# Schematic.net
KiCad netlist of a schematic drawn in Altium Designer
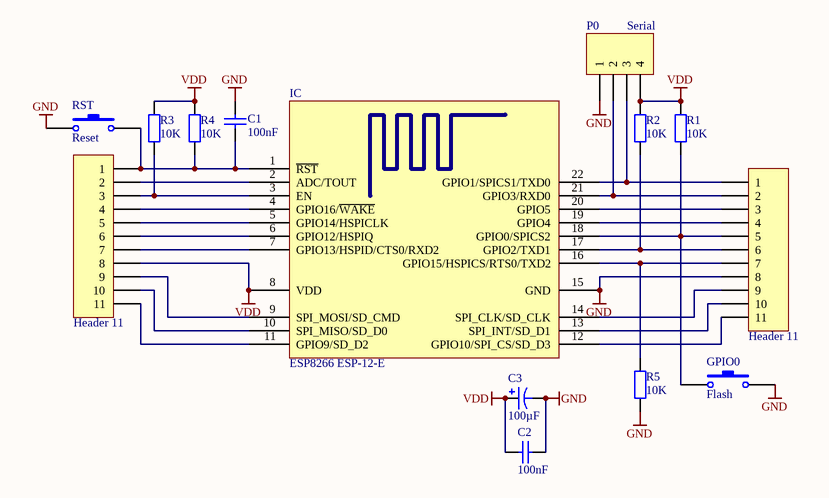
[diagram p0: Schematic.SchDoc]

(export (version "E")
  (design (tool "Eeschema 10.0.6"))
  (components
    (comp (ref "C1")
      (value "100nF")
      (footprint "C1206")
      (description "Capacitor (Semiconductor SIM Model)")
      (fields (field (name "Comment") "Cap Semi") (field (name "PUBLISHER") "Altium Limited"))
      (libsource (lib "Miscellaneous Devices") (part "Cap Semi"))
    )
    (comp (ref "C2")
      (value "100nF")
      (footprint "C1206")
      (description "Capacitor (Semiconductor SIM Model)")
      (fields (field (name "Comment") "Cap Semi") (field (name "PUBLISHER") "Altium Limited"))
      (libsource (lib "Miscellaneous Devices") (part "Cap Semi"))
    )
    (comp (ref "C3")
      (value "100µF")
      (footprint "SMD cap 6x5")
      (description "Polarized Capacitor (Radial)")
      (fields (field (name "PUBLISHER") "Altium Limited"))
      (libsource (lib "Miscellaneous Devices") (part "Cap Pol1"))
    )
    (comp (ref "GPIO0")
      (value "Flash")
      (footprint "SMDswitch")
      (description "Switch")
      (fields (field (name "PUBLISHER") "Altium Limited"))
      (libsource (lib "Miscellaneous Devices") (part "SW-PB"))
    )
    (comp (ref "IC")
      (value "ESP8266 ESP-12-E")
      (footprint "ESP8266 ESP-12-E")
      (libsource (lib "ESP8266") (part "ESP8266 ESP-12-E"))
    )
    (comp (ref "P0")
      (value "Serial")
      (footprint "HDR1X4")
      (description "Header, 4-Pin")
      (fields (field (name "PUBLISHER") "Altium Limited"))
      (libsource (lib "Miscellaneous Connectors") (part "Header 4"))
    )
    (comp (ref "P1")
      (value "Header 11")
      (footprint "HDR1X11")
      (description "Header, 11-Pin")
      (fields (field (name "PUBLISHER") "Altium Limited"))
      (libsource (lib "Miscellaneous Connectors") (part "Header 11"))
    )
    (comp (ref "P2")
      (value "Header 11")
      (footprint "HDR1X11")
      (description "Header, 11-Pin")
      (fields (field (name "PUBLISHER") "Altium Limited"))
      (libsource (lib "") (part "Header 11_1"))
    )
    (comp (ref "R1")
      (value "10K")
      (footprint "C1206")
      (description "Resistor")
      (fields (field (name "Comment") "Res2") (field (name "PUBLISHER") "Altium Limited"))
      (libsource (lib "Miscellaneous Devices") (part "Res2"))
    )
    (comp (ref "R2")
      (value "10K")
      (footprint "C1206")
      (description "Resistor")
      (fields (field (name "Comment") "Res2") (field (name "PUBLISHER") "Altium Limited"))
      (libsource (lib "Miscellaneous Devices") (part "Res2"))
    )
    (comp (ref "R3")
      (value "10K")
      (footprint "C1206")
      (description "Resistor")
      (fields (field (name "Comment") "Res2") (field (name "PUBLISHER") "Altium Limited"))
      (libsource (lib "Miscellaneous Devices") (part "Res2"))
    )
    (comp (ref "R4")
      (value "10K")
      (footprint "C1206")
      (description "Resistor")
      (fields (field (name "Comment") "Res2") (field (name "PUBLISHER") "Altium Limited"))
      (libsource (lib "Miscellaneous Devices") (part "Res2"))
    )
    (comp (ref "R5")
      (value "10K")
      (footprint "C1206")
      (description "Resistor")
      (fields (field (name "Comment") "Res2") (field (name "PUBLISHER") "Altium Limited"))
      (libsource (lib "Miscellaneous Devices") (part "Res2"))
    )
    (comp (ref "RST")
      (value "Reset")
      (footprint "SMDswitch")
      (description "Switch")
      (fields (field (name "PUBLISHER") "Altium Limited"))
      (libsource (lib "Miscellaneous Devices") (part "SW-PB"))
    )
  )
  (nets
    (net (code "1") (name "GND") (class "Default")
      (node (ref "C1") (pin "2") (pinfunction "2_2") (pintype "passive"))
      (node (ref "C2") (pin "2") (pinfunction "2_2") (pintype "passive"))
      (node (ref "C3") (pin "2") (pinfunction "2_2") (pintype "passive"))
      (node (ref "GPIO0") (pin "2") (pinfunction "2_2") (pintype "passive"))
      (node (ref "IC") (pin "15") (pinfunction "GND_15") (pintype "passive"))
      (node (ref "P0") (pin "1") (pinfunction "1_1") (pintype "passive"))
      (node (ref "P2") (pin "8") (pinfunction "8_8") (pintype "passive"))
      (node (ref "R5") (pin "1") (pinfunction "1_1") (pintype "passive"))
      (node (ref "RST") (pin "1") (pinfunction "1_1") (pintype "passive"))
    )
    (net (code "2") (name "Net-(IC-ADC{slash}TOUT)") (class "Default")
      (node (ref "IC") (pin "2") (pinfunction "ADC/TOUT_2") (pintype "passive"))
      (node (ref "P1") (pin "2") (pinfunction "2_2") (pintype "passive"))
    )
    (net (code "3") (name "Net-(IC-EN)") (class "Default")
      (node (ref "IC") (pin "3") (pinfunction "EN_3") (pintype "passive"))
      (node (ref "P1") (pin "3") (pinfunction "3_3") (pintype "passive"))
      (node (ref "R3") (pin "1") (pinfunction "1_1") (pintype "passive"))
    )
    (net (code "4") (name "Net-(IC-GPIO0{slash}SPICS2)") (class "Default")
      (node (ref "GPIO0") (pin "1") (pinfunction "1_1") (pintype "passive"))
      (node (ref "IC") (pin "18") (pinfunction "GPIO0/SPICS2_18") (pintype "passive"))
      (node (ref "P2") (pin "5") (pinfunction "5_5") (pintype "passive"))
      (node (ref "R1") (pin "1") (pinfunction "1_1") (pintype "passive"))
    )
    (net (code "5") (name "Net-(IC-GPIO1{slash}SPICS1{slash}TXD0)") (class "Default")
      (node (ref "IC") (pin "22") (pinfunction "GPIO1/SPICS1/TXD0_22") (pintype "passive"))
      (node (ref "P0") (pin "3") (pinfunction "3_3") (pintype "passive"))
      (node (ref "P2") (pin "1") (pinfunction "1_1") (pintype "passive"))
    )
    (net (code "6") (name "Net-(IC-GPIO2{slash}TXD1)") (class "Default")
      (node (ref "IC") (pin "17") (pinfunction "GPIO2/TXD1_17") (pintype "passive"))
      (node (ref "P2") (pin "6") (pinfunction "6_6") (pintype "passive"))
      (node (ref "R2") (pin "1") (pinfunction "1_1") (pintype "passive"))
    )
    (net (code "7") (name "Net-(IC-GPIO3{slash}RXD0)") (class "Default")
      (node (ref "IC") (pin "21") (pinfunction "GPIO3/RXD0_21") (pintype "passive"))
      (node (ref "P0") (pin "2") (pinfunction "2_2") (pintype "passive"))
      (node (ref "P2") (pin "2") (pinfunction "2_2") (pintype "passive"))
    )
    (net (code "8") (name "Net-(IC-GPIO4)") (class "Default")
      (node (ref "IC") (pin "19") (pinfunction "GPIO4_19") (pintype "passive"))
      (node (ref "P2") (pin "4") (pinfunction "4_4") (pintype "passive"))
    )
    (net (code "9") (name "Net-(IC-GPIO5)") (class "Default")
      (node (ref "IC") (pin "20") (pinfunction "GPIO5_20") (pintype "passive"))
      (node (ref "P2") (pin "3") (pinfunction "3_3") (pintype "passive"))
    )
    (net (code "10") (name "Net-(IC-GPIO9{slash}SD_D2)") (class "Default")
      (node (ref "IC") (pin "11") (pinfunction "GPIO9/SD_D2_11") (pintype "passive"))
      (node (ref "P1") (pin "11") (pinfunction "11_11") (pintype "passive"))
    )
    (net (code "11") (name "Net-(IC-GPIO10{slash}SPI_CS{slash}SD_D3)") (class "Default")
      (node (ref "IC") (pin "12") (pinfunction "GPIO10/SPI_CS/SD_D3_12") (pintype "passive"))
      (node (ref "P2") (pin "11") (pinfunction "11_11") (pintype "passive"))
    )
    (net (code "12") (name "Net-(IC-GPIO12{slash}HSPIQ)") (class "Default")
      (node (ref "IC") (pin "6") (pinfunction "GPIO12/HSPIQ_6") (pintype "passive"))
      (node (ref "P1") (pin "6") (pinfunction "6_6") (pintype "passive"))
    )
    (net (code "13") (name "Net-(IC-GPIO13{slash}HSPID{slash}CTS0{slash}RXD2)") (class "Default")
      (node (ref "IC") (pin "7") (pinfunction "GPIO13/HSPID/CTS0/RXD2_7") (pintype "passive"))
      (node (ref "P1") (pin "7") (pinfunction "7_7") (pintype "passive"))
    )
    (net (code "14") (name "Net-(IC-GPIO14{slash}HSPICLK)") (class "Default")
      (node (ref "IC") (pin "5") (pinfunction "GPIO14/HSPICLK_5") (pintype "passive"))
      (node (ref "P1") (pin "5") (pinfunction "5_5") (pintype "passive"))
    )
    (net (code "15") (name "Net-(IC-GPIO15{slash}HSPICS{slash}RTS0{slash}TXD2)") (class "Default")
      (node (ref "IC") (pin "16") (pinfunction "GPIO15/HSPICS/RTS0/TXD2_16") (pintype "passive"))
      (node (ref "P2") (pin "7") (pinfunction "7_7") (pintype "passive"))
      (node (ref "R5") (pin "2") (pinfunction "2_2") (pintype "passive"))
    )
    (net (code "16") (name "Net-(IC-GPIO16{slash}~{WAKE})") (class "Default")
      (node (ref "IC") (pin "4") (pinfunction "GPIO16/~{WAKE}_4") (pintype "passive"))
      (node (ref "P1") (pin "4") (pinfunction "4_4") (pintype "passive"))
    )
    (net (code "17") (name "Net-(IC-SPI_CLK{slash}SD_CLK)") (class "Default")
      (node (ref "IC") (pin "14") (pinfunction "SPI_CLK/SD_CLK_14") (pintype "passive"))
      (node (ref "P2") (pin "9") (pinfunction "9_9") (pintype "passive"))
    )
    (net (code "18") (name "Net-(IC-SPI_INT{slash}SD_D1)") (class "Default")
      (node (ref "IC") (pin "13") (pinfunction "SPI_INT/SD_D1_13") (pintype "passive"))
      (node (ref "P2") (pin "10") (pinfunction "10_10") (pintype "passive"))
    )
    (net (code "19") (name "Net-(IC-SPI_MISO{slash}SD_D0)") (class "Default")
      (node (ref "IC") (pin "10") (pinfunction "SPI_MISO/SD_D0_10") (pintype "passive"))
      (node (ref "P1") (pin "10") (pinfunction "10_10") (pintype "passive"))
    )
    (net (code "20") (name "Net-(IC-SPI_MOSI{slash}SD_CMD)") (class "Default")
      (node (ref "IC") (pin "9") (pinfunction "SPI_MOSI/SD_CMD_9") (pintype "passive"))
      (node (ref "P1") (pin "9") (pinfunction "9_9") (pintype "passive"))
    )
    (net (code "21") (name "Net-(IC-~{RST})") (class "Default")
      (node (ref "C1") (pin "1") (pinfunction "1_1") (pintype "passive"))
      (node (ref "IC") (pin "1") (pinfunction "~{RST}_1") (pintype "passive"))
      (node (ref "P1") (pin "1") (pinfunction "1_1") (pintype "passive"))
      (node (ref "R4") (pin "1") (pinfunction "1_1") (pintype "passive"))
      (node (ref "RST") (pin "2") (pinfunction "2_2") (pintype "passive"))
    )
    (net (code "22") (name "VDD") (class "Default")
      (node (ref "C2") (pin "1") (pinfunction "1_1") (pintype "passive"))
      (node (ref "C3") (pin "1") (pinfunction "1_1") (pintype "passive"))
      (node (ref "IC") (pin "8") (pinfunction "VDD_8") (pintype "passive"))
      (node (ref "P0") (pin "4") (pinfunction "4_4") (pintype "passive"))
      (node (ref "P1") (pin "8") (pinfunction "8_8") (pintype "passive"))
      (node (ref "R1") (pin "2") (pinfunction "2_2") (pintype "passive"))
      (node (ref "R2") (pin "2") (pinfunction "2_2") (pintype "passive"))
      (node (ref "R3") (pin "2") (pinfunction "2_2") (pintype "passive"))
      (node (ref "R4") (pin "2") (pinfunction "2_2") (pintype "passive"))
    )
  )
)
